# sensor_board_v1_3.net
KiCad netlist of a schematic drawn in EAGLE
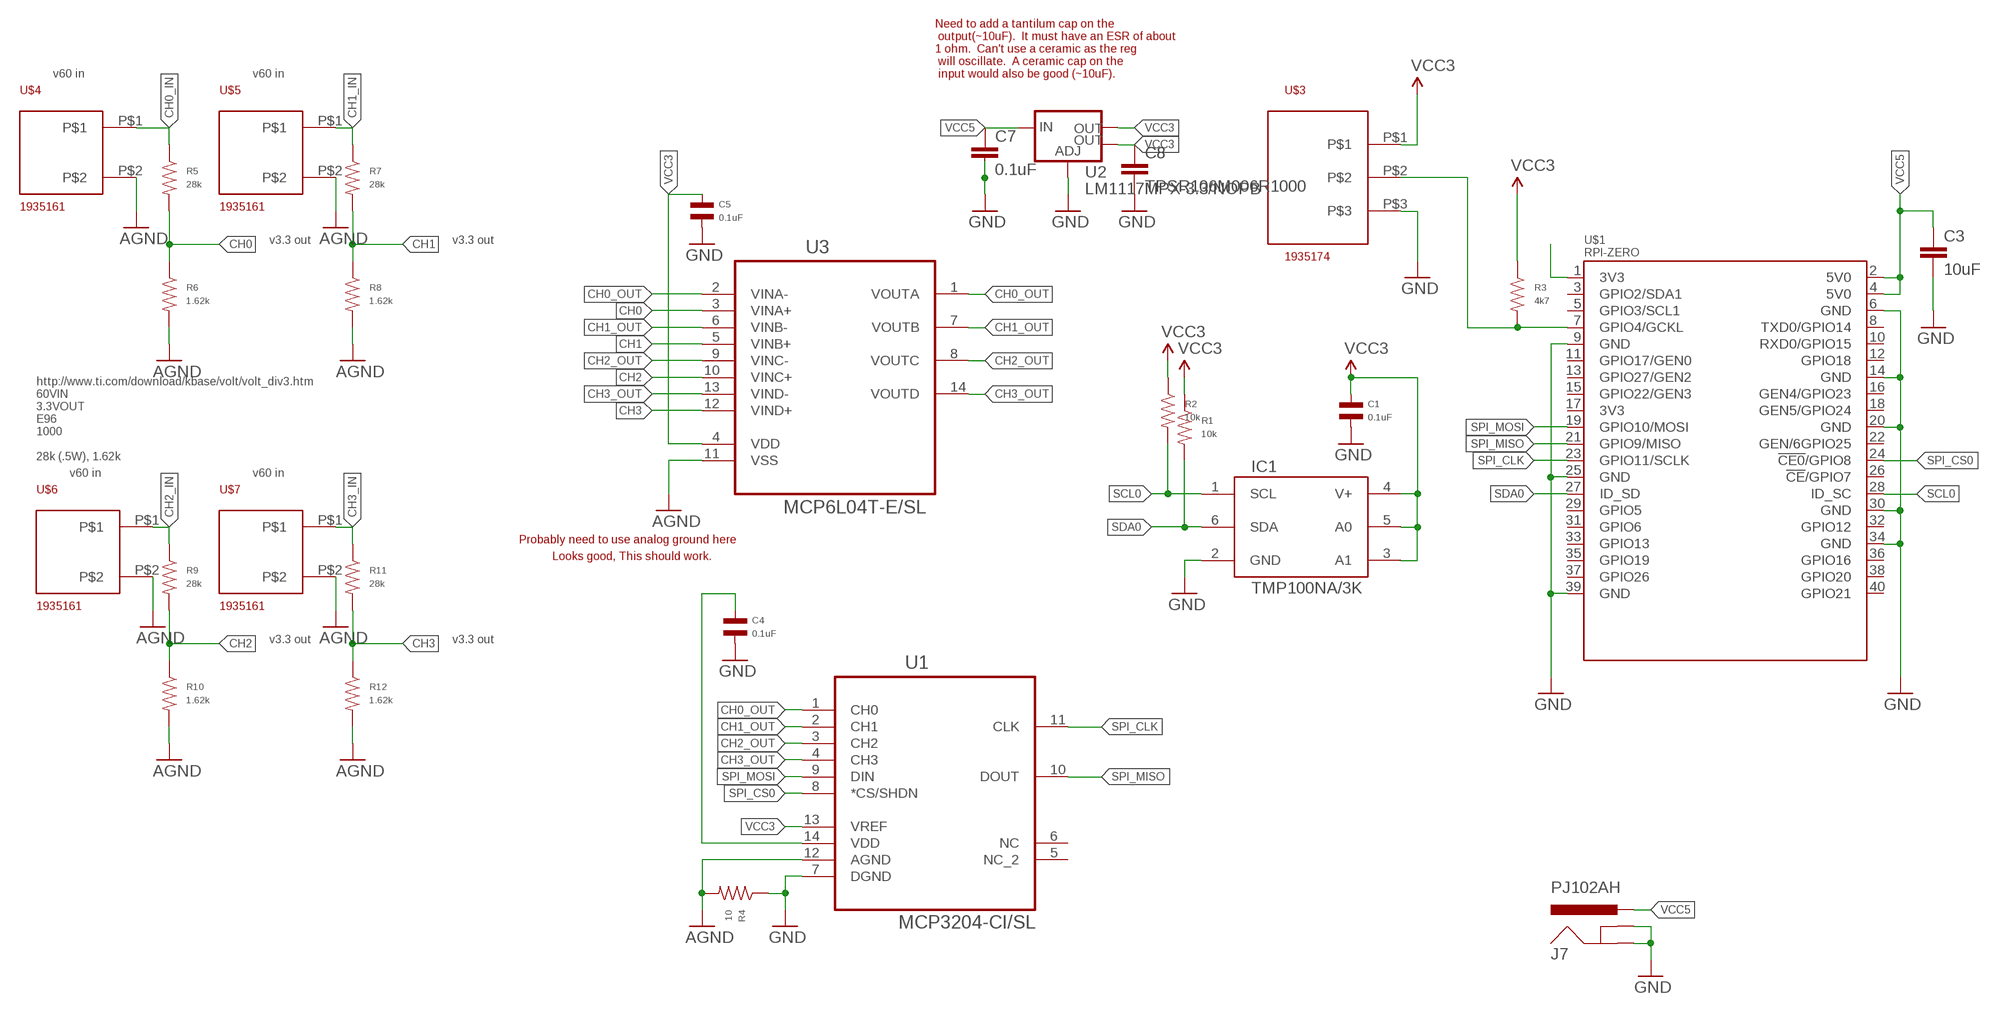
[diagram p0: schematic, sheet 1]

(export (version "E")
  (design (tool "Eeschema 10.0.6"))
  (components
    (comp (ref "C1")
      (value "0.1uF")
      (footprint "eagle-import:C0603")
      (libsource (lib "eagle-import") (part "CAPACITOR_NP_0603"))
    )
    (comp (ref "C3")
      (value "10uF")
      (footprint "eagle-import:0603-CAP")
      (libsource (lib "eagle-import") (part "CAP0603-CAP"))
    )
    (comp (ref "C4")
      (value "0.1uF")
      (footprint "eagle-import:C0603")
      (libsource (lib "eagle-import") (part "CAPACITOR_NP_0603"))
    )
    (comp (ref "C5")
      (value "0.1uF")
      (footprint "eagle-import:C0603")
      (libsource (lib "eagle-import") (part "CAPACITOR_NP_0603"))
    )
    (comp (ref "C7")
      (value "0.1uF")
      (footprint "eagle-import:0603-CAP")
      (libsource (lib "eagle-import") (part "CAP0603-CAP"))
    )
    (comp (ref "C8")
      (value "TPSR106M006R1000")
      (footprint "eagle-import:0805")
      (libsource (lib "eagle-import") (part "CAP0805"))
    )
    (comp (ref "IC1")
      (value "TMP100NA/3K")
      (footprint "eagle-import:TI-DBV")
      (libsource (lib "eagle-import") (part "TMP100"))
    )
    (comp (ref "J7")
      (value "PJ102AH")
      (footprint "eagle-import:PJ-102AH")
      (libsource (lib "eagle-import") (part "POWER_JACK"))
    )
    (comp (ref "R1")
      (value "10k")
      (footprint "eagle-import:R0603")
      (libsource (lib "eagle-import") (part "RESISTOR_0603"))
    )
    (comp (ref "R2")
      (value "10k")
      (footprint "eagle-import:R0603")
      (libsource (lib "eagle-import") (part "RESISTOR_0603"))
    )
    (comp (ref "R3")
      (value "4k7")
      (footprint "eagle-import:R0603")
      (libsource (lib "eagle-import") (part "RESISTOR_0603"))
    )
    (comp (ref "R4")
      (value "10")
      (footprint "eagle-import:R1206")
      (libsource (lib "eagle-import") (part "RESISTOR_1206"))
    )
    (comp (ref "R5")
      (value "28k")
      (footprint "eagle-import:R1206")
      (fields (field (name "MPN") "RNCP1206FTD28K0"))
      (libsource (lib "eagle-import") (part "RESISTOR_1206"))
    )
    (comp (ref "R6")
      (value "1.62k")
      (footprint "eagle-import:R1206")
      (libsource (lib "eagle-import") (part "RESISTOR_1206"))
    )
    (comp (ref "R7")
      (value "28k")
      (footprint "eagle-import:R1206")
      (fields (field (name "MPN") "RNCP1206FTD28K0"))
      (libsource (lib "eagle-import") (part "RESISTOR_1206"))
    )
    (comp (ref "R8")
      (value "1.62k")
      (footprint "eagle-import:R1206")
      (libsource (lib "eagle-import") (part "RESISTOR_1206"))
    )
    (comp (ref "R9")
      (value "28k")
      (footprint "eagle-import:R1206")
      (fields (field (name "MPN") "RNCP1206FTD28K0"))
      (libsource (lib "eagle-import") (part "RESISTOR_1206"))
    )
    (comp (ref "R10")
      (value "1.62k")
      (footprint "eagle-import:R1206")
      (libsource (lib "eagle-import") (part "RESISTOR_1206"))
    )
    (comp (ref "R11")
      (value "28k")
      (footprint "eagle-import:R1206")
      (fields (field (name "MPN") "RNCP1206FTD28K0"))
      (libsource (lib "eagle-import") (part "RESISTOR_1206"))
    )
    (comp (ref "R12")
      (value "1.62k")
      (footprint "eagle-import:R1206")
      (libsource (lib "eagle-import") (part "RESISTOR_1206"))
    )
    (comp (ref "U$1")
      (value "RPI-ZERO")
      (footprint "eagle-import:RASPBERRYPI_BASTELSTUBE_V13_RASPI_BOARD_B+_FULL")
      (libsource (lib "eagle-import") (part "RPI-ZERO"))
    )
    (comp (ref "U$3")
      (value "1935174")
      (footprint "eagle-import:1935174")
      (libsource (lib "eagle-import") (part "1935174"))
    )
    (comp (ref "U$4")
      (value "1935161")
      (footprint "eagle-import:1935161")
      (libsource (lib "eagle-import") (part "1935161"))
    )
    (comp (ref "U$5")
      (value "1935161")
      (footprint "eagle-import:1935161")
      (libsource (lib "eagle-import") (part "1935161"))
    )
    (comp (ref "U$6")
      (value "1935161")
      (footprint "eagle-import:1935161")
      (libsource (lib "eagle-import") (part "1935161"))
    )
    (comp (ref "U$7")
      (value "1935161")
      (footprint "eagle-import:1935161")
      (libsource (lib "eagle-import") (part "1935161"))
    )
    (comp (ref "U1")
      (value "MCP3204-CI/SL")
      (footprint "eagle-import:SOIC127P600X175-14N")
      (libsource (lib "eagle-import") (part "MCP3204-CI/SL"))
    )
    (comp (ref "U2")
      (value "LM1117MPX-3.3/NOPB")
      (footprint "eagle-import:SOT223")
      (fields (field (name "PROD_ID") "LM1117MPX-3.3/NOPB"))
      (libsource (lib "eagle-import") (part "V_REG_LM1117SOT223"))
    )
    (comp (ref "U3")
      (value "MCP6L04T-E/SL")
      (footprint "eagle-import:SOIC127P600X175-14N")
      (libsource (lib "eagle-import") (part "MCP6L04T-E/SL"))
    )
  )
  (nets
    (net (code "1") (name "/3V3") (class "Default")
      (node (ref "U$1") (pin "17") (pinfunction "3V3_17") (pintype "power_in"))
    )
    (net (code "2") (name "AGND") (class "Default")
      (node (ref "R10") (pin "P$2") (pinfunction "P$2_P$2") (pintype "passive"))
      (node (ref "R12") (pin "P$2") (pinfunction "P$2_P$2") (pintype "passive"))
      (node (ref "R4") (pin "P$2") (pinfunction "P$2_P$2") (pintype "passive"))
      (node (ref "R6") (pin "P$2") (pinfunction "P$2_P$2") (pintype "passive"))
      (node (ref "R8") (pin "P$2") (pinfunction "P$2_P$2") (pintype "passive"))
      (node (ref "U$4") (pin "P$2") (pinfunction "P$2_P$2") (pintype "bidirectional"))
      (node (ref "U$5") (pin "P$2") (pinfunction "P$2_P$2") (pintype "bidirectional"))
      (node (ref "U$6") (pin "P$2") (pinfunction "P$2_P$2") (pintype "bidirectional"))
      (node (ref "U$7") (pin "P$2") (pinfunction "P$2_P$2") (pintype "bidirectional"))
      (node (ref "U1") (pin "12") (pinfunction "AGND_12") (pintype "passive"))
      (node (ref "U3") (pin "11") (pinfunction "VSS_11") (pintype "passive"))
    )
    (net (code "3") (name "CH0") (class "Default")
      (node (ref "R5") (pin "P$2") (pinfunction "P$2_P$2") (pintype "passive"))
      (node (ref "R6") (pin "P$1") (pinfunction "P$1_P$1") (pintype "passive"))
      (node (ref "U3") (pin "3") (pinfunction "VINA+_3") (pintype "input"))
    )
    (net (code "4") (name "CH0_IN") (class "Default")
      (node (ref "R5") (pin "P$1") (pinfunction "P$1_P$1") (pintype "passive"))
      (node (ref "U$4") (pin "P$1") (pinfunction "P$1_P$1") (pintype "bidirectional"))
    )
    (net (code "5") (name "CH0_OUT") (class "Default")
      (node (ref "U1") (pin "1") (pinfunction "CH0_1") (pintype "input"))
      (node (ref "U3") (pin "1") (pinfunction "VOUTA_1") (pintype "output"))
      (node (ref "U3") (pin "2") (pinfunction "VINA-_2") (pintype "input"))
    )
    (net (code "6") (name "CH1") (class "Default")
      (node (ref "R7") (pin "P$2") (pinfunction "P$2_P$2") (pintype "passive"))
      (node (ref "R8") (pin "P$1") (pinfunction "P$1_P$1") (pintype "passive"))
      (node (ref "U3") (pin "5") (pinfunction "VINB+_5") (pintype "input"))
    )
    (net (code "7") (name "CH1_IN") (class "Default")
      (node (ref "R7") (pin "P$1") (pinfunction "P$1_P$1") (pintype "passive"))
      (node (ref "U$5") (pin "P$1") (pinfunction "P$1_P$1") (pintype "bidirectional"))
    )
    (net (code "8") (name "CH1_OUT") (class "Default")
      (node (ref "U1") (pin "2") (pinfunction "CH1_2") (pintype "input"))
      (node (ref "U3") (pin "6") (pinfunction "VINB-_6") (pintype "input"))
      (node (ref "U3") (pin "7") (pinfunction "VOUTB_7") (pintype "output"))
    )
    (net (code "9") (name "CH2") (class "Default")
      (node (ref "R10") (pin "P$1") (pinfunction "P$1_P$1") (pintype "passive"))
      (node (ref "R9") (pin "P$2") (pinfunction "P$2_P$2") (pintype "passive"))
      (node (ref "U3") (pin "10") (pinfunction "VINC+_10") (pintype "input"))
    )
    (net (code "10") (name "CH2_IN") (class "Default")
      (node (ref "R9") (pin "P$1") (pinfunction "P$1_P$1") (pintype "passive"))
      (node (ref "U$6") (pin "P$1") (pinfunction "P$1_P$1") (pintype "bidirectional"))
    )
    (net (code "11") (name "CH2_OUT") (class "Default")
      (node (ref "U1") (pin "3") (pinfunction "CH2_3") (pintype "input"))
      (node (ref "U3") (pin "8") (pinfunction "VOUTC_8") (pintype "output"))
      (node (ref "U3") (pin "9") (pinfunction "VINC-_9") (pintype "input"))
    )
    (net (code "12") (name "CH3") (class "Default")
      (node (ref "R11") (pin "P$2") (pinfunction "P$2_P$2") (pintype "passive"))
      (node (ref "R12") (pin "P$1") (pinfunction "P$1_P$1") (pintype "passive"))
      (node (ref "U3") (pin "12") (pinfunction "VIND+_12") (pintype "input"))
    )
    (net (code "13") (name "CH3_IN") (class "Default")
      (node (ref "R11") (pin "P$1") (pinfunction "P$1_P$1") (pintype "passive"))
      (node (ref "U$7") (pin "P$1") (pinfunction "P$1_P$1") (pintype "bidirectional"))
    )
    (net (code "14") (name "CH3_OUT") (class "Default")
      (node (ref "U1") (pin "4") (pinfunction "CH3_4") (pintype "input"))
      (node (ref "U3") (pin "13") (pinfunction "VIND-_13") (pintype "input"))
      (node (ref "U3") (pin "14") (pinfunction "VOUTD_14") (pintype "output"))
    )
    (net (code "15") (name "GND") (class "Default")
      (node (ref "C1") (pin "P$2") (pinfunction "P$2_P$2") (pintype "passive"))
      (node (ref "C3") (pin "2") (pinfunction "2_2") (pintype "passive"))
      (node (ref "C4") (pin "P$2") (pinfunction "P$2_P$2") (pintype "passive"))
      (node (ref "C5") (pin "P$2") (pinfunction "P$2_P$2") (pintype "passive"))
      (node (ref "C7") (pin "2") (pinfunction "2_2") (pintype "passive"))
      (node (ref "C8") (pin "2") (pinfunction "2_2") (pintype "passive"))
      (node (ref "IC1") (pin "2") (pinfunction "GND_2") (pintype "bidirectional"))
      (node (ref "J7") (pin "2") (pinfunction "GND_2") (pintype "bidirectional"))
      (node (ref "J7") (pin "3") (pinfunction "GNDBREAK_3") (pintype "bidirectional"))
      (node (ref "R4") (pin "P$1") (pinfunction "P$1_P$1") (pintype "passive"))
      (node (ref "U$1") (pin "14") (pinfunction "GND_14") (pintype "power_in"))
      (node (ref "U$1") (pin "20") (pinfunction "GND_20") (pintype "power_in"))
      (node (ref "U$1") (pin "25") (pinfunction "GND_25") (pintype "power_in"))
      (node (ref "U$1") (pin "30") (pinfunction "GND_30") (pintype "power_in"))
      (node (ref "U$1") (pin "34") (pinfunction "GND_34") (pintype "power_in"))
      (node (ref "U$1") (pin "39") (pinfunction "GND_39") (pintype "power_in"))
      (node (ref "U$1") (pin "6") (pinfunction "GND_6") (pintype "power_in"))
      (node (ref "U$1") (pin "9") (pinfunction "GND_9") (pintype "power_in"))
      (node (ref "U$3") (pin "P$3") (pinfunction "P$3_P$3") (pintype "bidirectional"))
      (node (ref "U1") (pin "7") (pinfunction "DGND_7") (pintype "passive"))
      (node (ref "U2") (pin "1") (pinfunction "ADJ_1") (pintype "input"))
    )
    (net (code "16") (name "Net-(U$1-GPIO4{slash}GCKL)") (class "Default")
      (node (ref "R3") (pin "P$2") (pinfunction "P$2_P$2") (pintype "passive"))
      (node (ref "U$1") (pin "7") (pinfunction "GPIO4/GCKL_7") (pintype "bidirectional"))
      (node (ref "U$3") (pin "P$2") (pinfunction "P$2_P$2") (pintype "bidirectional"))
    )
    (net (code "17") (name "SCL0") (class "Default")
      (node (ref "IC1") (pin "1") (pinfunction "SCL_1") (pintype "bidirectional"))
      (node (ref "R2") (pin "P$2") (pinfunction "P$2_P$2") (pintype "passive"))
      (node (ref "U$1") (pin "28") (pinfunction "ID_SC_28") (pintype "bidirectional"))
    )
    (net (code "18") (name "SDA0") (class "Default")
      (node (ref "IC1") (pin "6") (pinfunction "SDA_6") (pintype "bidirectional"))
      (node (ref "R1") (pin "P$2") (pinfunction "P$2_P$2") (pintype "passive"))
      (node (ref "U$1") (pin "27") (pinfunction "ID_SD_27") (pintype "bidirectional"))
    )
    (net (code "19") (name "SPI_CLK") (class "Default")
      (node (ref "U$1") (pin "23") (pinfunction "GPIO11/SCLK_23") (pintype "bidirectional"))
      (node (ref "U1") (pin "11") (pinfunction "CLK_11") (pintype "input"))
    )
    (net (code "20") (name "SPI_CS0") (class "Default")
      (node (ref "U$1") (pin "24") (pinfunction "~{CE0}/GPIO8_24") (pintype "bidirectional"))
      (node (ref "U1") (pin "8") (pinfunction "*CS/SHDN_8") (pintype "input"))
    )
    (net (code "21") (name "SPI_MISO") (class "Default")
      (node (ref "U$1") (pin "21") (pinfunction "GPIO9/MISO_21") (pintype "bidirectional"))
      (node (ref "U1") (pin "10") (pinfunction "DOUT_10") (pintype "output"))
    )
    (net (code "22") (name "SPI_MOSI") (class "Default")
      (node (ref "U$1") (pin "19") (pinfunction "GPIO10/MOSI_19") (pintype "bidirectional"))
      (node (ref "U1") (pin "9") (pinfunction "DIN_9") (pintype "input"))
    )
    (net (code "23") (name "VCC3") (class "Default")
      (node (ref "C1") (pin "P$1") (pinfunction "P$1_P$1") (pintype "passive"))
      (node (ref "C4") (pin "P$1") (pinfunction "P$1_P$1") (pintype "passive"))
      (node (ref "C5") (pin "P$1") (pinfunction "P$1_P$1") (pintype "passive"))
      (node (ref "C8") (pin "1") (pinfunction "1_1") (pintype "passive"))
      (node (ref "IC1") (pin "3") (pinfunction "A1_3") (pintype "bidirectional"))
      (node (ref "IC1") (pin "4") (pinfunction "V+_4") (pintype "bidirectional"))
      (node (ref "IC1") (pin "5") (pinfunction "A0_5") (pintype "bidirectional"))
      (node (ref "R1") (pin "P$1") (pinfunction "P$1_P$1") (pintype "passive"))
      (node (ref "R2") (pin "P$1") (pinfunction "P$1_P$1") (pintype "passive"))
      (node (ref "R3") (pin "P$1") (pinfunction "P$1_P$1") (pintype "passive"))
      (node (ref "U$1") (pin "1") (pinfunction "3V3_1") (pintype "power_in"))
      (node (ref "U$3") (pin "P$1") (pinfunction "P$1_P$1") (pintype "bidirectional"))
      (node (ref "U1") (pin "13") (pinfunction "VREF_13") (pintype "input"))
      (node (ref "U1") (pin "14") (pinfunction "VDD_14") (pintype "power_in"))
      (node (ref "U2") (pin "2") (pinfunction "OUT_2") (pintype "output"))
      (node (ref "U2") (pin "4") (pinfunction "OUT_4") (pintype "output"))
      (node (ref "U3") (pin "4") (pinfunction "VDD_4") (pintype "power_in"))
    )
    (net (code "24") (name "VCC5") (class "Default")
      (node (ref "C3") (pin "1") (pinfunction "1_1") (pintype "passive"))
      (node (ref "C7") (pin "1") (pinfunction "1_1") (pintype "passive"))
      (node (ref "J7") (pin "1") (pinfunction "PWR_1") (pintype "bidirectional"))
      (node (ref "U$1") (pin "2") (pinfunction "5V0_2") (pintype "power_in"))
      (node (ref "U$1") (pin "4") (pinfunction "5V0_4") (pintype "power_in"))
      (node (ref "U2") (pin "3") (pinfunction "IN_3") (pintype "input"))
    )
    (net (code "25") (name "unconnected-(U$1-GEN4{slash}GPIO23-Pad16)") (class "Default")
      (node (ref "U$1") (pin "16") (pinfunction "GEN4/GPIO23_16") (pintype "bidirectional"))
    )
    (net (code "26") (name "unconnected-(U$1-GEN5{slash}GPIO24-Pad18)") (class "Default")
      (node (ref "U$1") (pin "18") (pinfunction "GEN5/GPIO24_18") (pintype "bidirectional"))
    )
    (net (code "27") (name "unconnected-(U$1-GEN{slash}6GPIO25-Pad22)") (class "Default")
      (node (ref "U$1") (pin "22") (pinfunction "GEN/6GPIO25_22") (pintype "bidirectional"))
    )
    (net (code "28") (name "unconnected-(U$1-GPIO2{slash}SDA1-Pad3)") (class "Default")
      (node (ref "U$1") (pin "3") (pinfunction "GPIO2/SDA1_3") (pintype "bidirectional"))
    )
    (net (code "29") (name "unconnected-(U$1-GPIO3{slash}SCL1-Pad5)") (class "Default")
      (node (ref "U$1") (pin "5") (pinfunction "GPIO3/SCL1_5") (pintype "bidirectional"))
    )
    (net (code "30") (name "unconnected-(U$1-GPIO5-Pad29)") (class "Default")
      (node (ref "U$1") (pin "29") (pinfunction "GPIO5_29") (pintype "bidirectional"))
    )
    (net (code "31") (name "unconnected-(U$1-GPIO6-Pad31)") (class "Default")
      (node (ref "U$1") (pin "31") (pinfunction "GPIO6_31") (pintype "bidirectional"))
    )
    (net (code "32") (name "unconnected-(U$1-GPIO12-Pad32)") (class "Default")
      (node (ref "U$1") (pin "32") (pinfunction "GPIO12_32") (pintype "bidirectional"))
    )
    (net (code "33") (name "unconnected-(U$1-GPIO13-Pad33)") (class "Default")
      (node (ref "U$1") (pin "33") (pinfunction "GPIO13_33") (pintype "bidirectional"))
    )
    (net (code "34") (name "unconnected-(U$1-GPIO16-Pad36)") (class "Default")
      (node (ref "U$1") (pin "36") (pinfunction "GPIO16_36") (pintype "bidirectional"))
    )
    (net (code "35") (name "unconnected-(U$1-GPIO17{slash}GEN0-Pad11)") (class "Default")
      (node (ref "U$1") (pin "11") (pinfunction "GPIO17/GEN0_11") (pintype "bidirectional"))
    )
    (net (code "36") (name "unconnected-(U$1-GPIO18-Pad12)") (class "Default")
      (node (ref "U$1") (pin "12") (pinfunction "GPIO18_12") (pintype "bidirectional"))
    )
    (net (code "37") (name "unconnected-(U$1-GPIO19-Pad35)") (class "Default")
      (node (ref "U$1") (pin "35") (pinfunction "GPIO19_35") (pintype "bidirectional"))
    )
    (net (code "38") (name "unconnected-(U$1-GPIO20-Pad38)") (class "Default")
      (node (ref "U$1") (pin "38") (pinfunction "GPIO20_38") (pintype "bidirectional"))
    )
    (net (code "39") (name "unconnected-(U$1-GPIO21-Pad40)") (class "Default")
      (node (ref "U$1") (pin "40") (pinfunction "GPIO21_40") (pintype "bidirectional"))
    )
    (net (code "40") (name "unconnected-(U$1-GPIO22{slash}GEN3-Pad15)") (class "Default")
      (node (ref "U$1") (pin "15") (pinfunction "GPIO22/GEN3_15") (pintype "bidirectional"))
    )
    (net (code "41") (name "unconnected-(U$1-GPIO26-Pad37)") (class "Default")
      (node (ref "U$1") (pin "37") (pinfunction "GPIO26_37") (pintype "bidirectional"))
    )
    (net (code "42") (name "unconnected-(U$1-GPIO27{slash}GEN2-Pad13)") (class "Default")
      (node (ref "U$1") (pin "13") (pinfunction "GPIO27/GEN2_13") (pintype "bidirectional"))
    )
    (net (code "43") (name "unconnected-(U$1-RXD0{slash}GPIO15-Pad10)") (class "Default")
      (node (ref "U$1") (pin "10") (pinfunction "RXD0/GPIO15_10") (pintype "bidirectional"))
    )
    (net (code "44") (name "unconnected-(U$1-TXD0{slash}GPIO14-Pad8)") (class "Default")
      (node (ref "U$1") (pin "8") (pinfunction "TXD0/GPIO14_8") (pintype "bidirectional"))
    )
    (net (code "45") (name "unconnected-(U$1-~{CE}{slash}GPIO7-Pad26)") (class "Default")
      (node (ref "U$1") (pin "26") (pinfunction "~{CE}/GPIO7_26") (pintype "bidirectional"))
    )
    (net (code "46") (name "unconnected-(U1-NC-Pad6)") (class "Default")
      (node (ref "U1") (pin "6") (pinfunction "NC_6") (pintype "no_connect"))
    )
    (net (code "47") (name "unconnected-(U1-NC_2-Pad5)") (class "Default")
      (node (ref "U1") (pin "5") (pinfunction "NC_2_5") (pintype "no_connect"))
    )
  )
)
